# PWR_P12V0A_N12V0A.net
KiCad netlist of a schematic drawn in Altium Designer
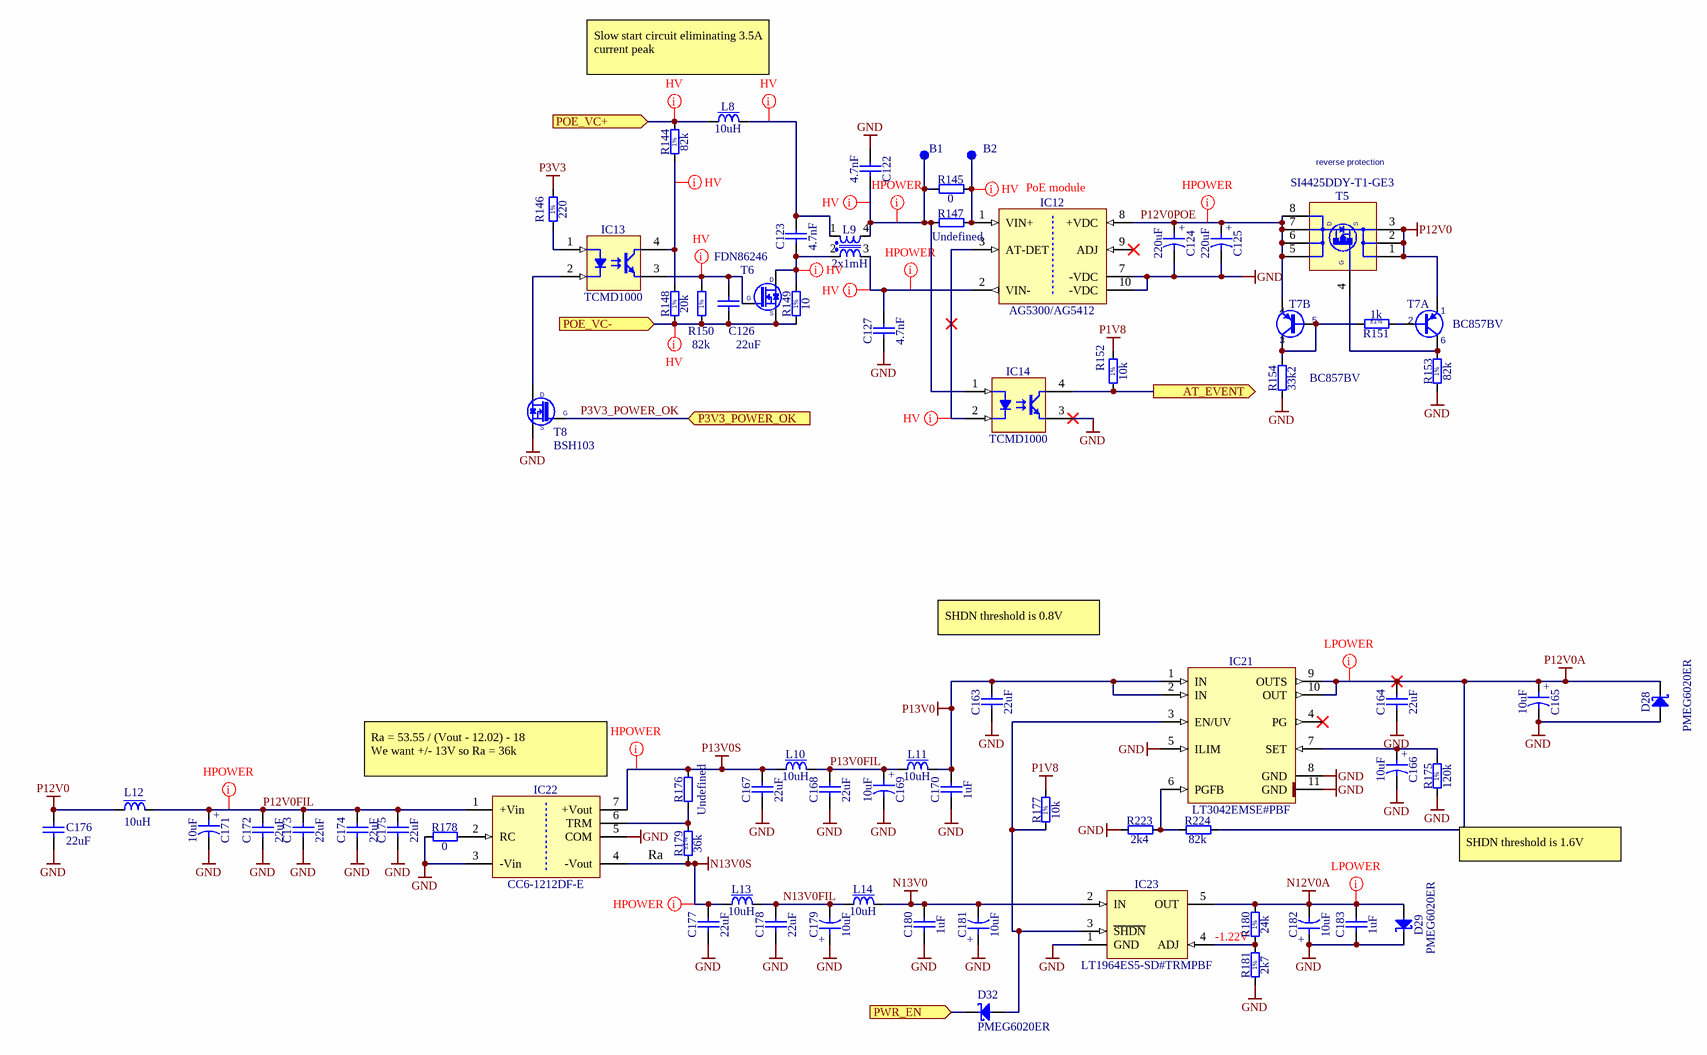
[diagram p0: PWR_P12V0A_N12V0A.SchDoc]

(export (version "E")
  (design (tool "Eeschema 10.0.6"))
  (components
    (comp (ref "B1")
      (value "SMD Pad")
      (footprint "C100")
      (description "Through Hole Pad")
      (fields (field (name "PART NUMBER") "SMD_PAD_D1MM") (field (name "AUTHOR") "CERN DEM JLC"))
      (libsource (lib "Eletro-mechanical") (part "Single SMD Pad (Round)"))
    )
    (comp (ref "B2")
      (value "SMD Pad")
      (footprint "C100")
      (description "Through Hole Pad")
      (fields (field (name "PART NUMBER") "SMD_PAD_D1MM") (field (name "AUTHOR") "CERN DEM JLC"))
      (libsource (lib "Eletro-mechanical") (part "Single SMD Pad (Round)"))
    )
    (comp (ref "C122")
      (value "4.7nF")
      (footprint "CAPC3216X140N")
      (description "Non-polarised capacitor")
      (fields
        (field (name "PART NUMBER") "CC1206_4.7NF_500V_10%_X7R")
        (field (name "VOLTAGE") "500V")
        (field (name "AUTHOR") "GK")
      )
      (libsource (lib "LIBRARY_SCH") (part "CAP_SMD_1206_4.7n_500V"))
    )
    (comp (ref "C123")
      (value "4.7nF")
      (footprint "CAPC3216X140N")
      (description "Non-polarised capacitor")
      (fields
        (field (name "PART NUMBER") "CC1206_4.7NF_500V_10%_X7R")
        (field (name "VOLTAGE") "500V")
        (field (name "AUTHOR") "GK")
      )
      (libsource (lib "LIBRARY_SCH") (part "CAP_SMD_1206_4.7n_500V"))
    )
    (comp (ref "C124")
      (value "220uF")
      (footprint "CAPAE830X620N")
      (description "Polarised capacitor")
      (fields
        (field (name "PART NUMBER") "CAE830-620_220UF_16V_20%")
        (field (name "VOLTAGE") "16V")
        (field (name "AUTHOR") "CERN DEM JLC")
      )
      (libsource (lib "Capacitors") (part "Capacitor - polarized"))
    )
    (comp (ref "C125")
      (value "220uF")
      (footprint "CAPAE830X620N")
      (description "Polarised capacitor")
      (fields
        (field (name "PART NUMBER") "CAE830-620_220UF_16V_20%")
        (field (name "VOLTAGE") "16V")
        (field (name "AUTHOR") "CERN DEM JLC")
      )
      (libsource (lib "Capacitors") (part "Capacitor - polarized"))
    )
    (comp (ref "C126")
      (value "22uF")
      (footprint "CAPC2012X135N")
      (description "Non-polarised capacitor")
      (fields
        (field (name "PART NUMBER") "CC0805_22UF_16V_10%_X5R")
        (field (name "VOLTAGE") "16V")
        (field (name "AUTHOR") "CERN DEM JLC")
      )
      (libsource (lib "Capacitors") (part "Capacitor - non polarized"))
    )
    (comp (ref "C127")
      (value "4.7nF")
      (footprint "CAPC3216X140N")
      (description "Non-polarised capacitor")
      (fields
        (field (name "PART NUMBER") "CC1206_4.7NF_500V_10%_X7R")
        (field (name "VOLTAGE") "500V")
        (field (name "AUTHOR") "GK")
      )
      (libsource (lib "LIBRARY_SCH") (part "CAP_SMD_1206_4.7n_500V"))
    )
    (comp (ref "C163")
      (value "22uF")
      (footprint "CAPC2012X135N")
      (description "Non-polarised capacitor")
      (fields
        (field (name "PART NUMBER") "CC0805_22UF_16V_10%_X5R")
        (field (name "VOLTAGE") "16V")
        (field (name "AUTHOR") "CERN DEM JLC")
      )
      (libsource (lib "Capacitors") (part "Capacitor - non polarized"))
    )
    (comp (ref "C164")
      (value "22uF")
      (footprint "CAPC2012X135N")
      (description "Non-polarised capacitor")
      (fields
        (field (name "PART NUMBER") "CC0805_22UF_16V_10%_X5R")
        (field (name "VOLTAGE") "16V")
        (field (name "AUTHOR") "CERN DEM JLC")
      )
      (libsource (lib "Capacitors") (part "Capacitor - non polarized"))
    )
    (comp (ref "C165")
      (value "10uF")
      (footprint "CAPMP3216X180N")
      (description "Polarised capacitor")
      (fields
        (field (name "PART NUMBER") "CTE3216-18_10UF_16V_20%_AVX_TCJ")
        (field (name "VOLTAGE") "16V")
        (field (name "AUTHOR") "CERN DEM JLC")
      )
      (libsource (lib "Capacitors") (part "Capacitor - polarized"))
    )
    (comp (ref "C166")
      (value "10uF")
      (footprint "CAPMP3216X180N")
      (description "Polarised capacitor")
      (fields
        (field (name "PART NUMBER") "CTE3216-18_10UF_16V_20%_AVX_TCJ")
        (field (name "VOLTAGE") "16V")
        (field (name "AUTHOR") "CERN DEM JLC")
      )
      (libsource (lib "Capacitors") (part "Capacitor - polarized"))
    )
    (comp (ref "C167")
      (value "22uF")
      (footprint "CAPC2012X135N")
      (description "Non-polarised capacitor")
      (fields
        (field (name "PART NUMBER") "CC0805_22UF_16V_10%_X5R")
        (field (name "VOLTAGE") "16V")
        (field (name "AUTHOR") "CERN DEM JLC")
      )
      (libsource (lib "Capacitors") (part "Capacitor - non polarized"))
    )
    (comp (ref "C168")
      (value "22uF")
      (footprint "CAPC2012X135N")
      (description "Non-polarised capacitor")
      (fields
        (field (name "PART NUMBER") "CC0805_22UF_16V_10%_X5R")
        (field (name "VOLTAGE") "16V")
        (field (name "AUTHOR") "CERN DEM JLC")
      )
      (libsource (lib "Capacitors") (part "Capacitor - non polarized"))
    )
    (comp (ref "C169")
      (value "10uF")
      (footprint "CAPMP3216X180N")
      (description "Polarised capacitor")
      (fields
        (field (name "PART NUMBER") "CTE3216-18_10UF_16V_20%_AVX_TCJ")
        (field (name "VOLTAGE") "16V")
        (field (name "AUTHOR") "CERN DEM JLC")
      )
      (libsource (lib "Capacitors") (part "Capacitor - polarized"))
    )
    (comp (ref "C170")
      (value "1uF")
      (footprint "CAPC1005X55N")
      (description "Non-polarised capacitor")
      (fields
        (field (name "PART NUMBER") "CC0402_1UF_16V_10%_X5R")
        (field (name "VOLTAGE") "16V")
        (field (name "AUTHOR") "CERN DEM JLC")
      )
      (libsource (lib "Capacitors") (part "Capacitor - non polarized"))
    )
    (comp (ref "C171")
      (value "10uF")
      (footprint "CAPMP3216X180N")
      (description "Polarised capacitor")
      (fields
        (field (name "PART NUMBER") "CTE3216-18_10UF_16V_20%_AVX_TCJ")
        (field (name "VOLTAGE") "16V")
        (field (name "AUTHOR") "CERN DEM JLC")
      )
      (libsource (lib "Capacitors") (part "Capacitor - polarized"))
    )
    (comp (ref "C172")
      (value "22uF")
      (footprint "CAPC2012X135N")
      (description "Non-polarised capacitor")
      (fields
        (field (name "PART NUMBER") "CC0805_22UF_16V_10%_X5R")
        (field (name "VOLTAGE") "16V")
        (field (name "AUTHOR") "CERN DEM JLC")
      )
      (libsource (lib "Capacitors") (part "Capacitor - non polarized"))
    )
    (comp (ref "C173")
      (value "22uF")
      (footprint "CAPC2012X135N")
      (description "Non-polarised capacitor")
      (fields
        (field (name "PART NUMBER") "CC0805_22UF_16V_10%_X5R")
        (field (name "VOLTAGE") "16V")
        (field (name "AUTHOR") "CERN DEM JLC")
      )
      (libsource (lib "Capacitors") (part "Capacitor - non polarized"))
    )
    (comp (ref "C174")
      (value "22uF")
      (footprint "CAPC2012X135N")
      (description "Non-polarised capacitor")
      (fields
        (field (name "PART NUMBER") "CC0805_22UF_16V_10%_X5R")
        (field (name "VOLTAGE") "16V")
        (field (name "AUTHOR") "CERN DEM JLC")
      )
      (libsource (lib "Capacitors") (part "Capacitor - non polarized"))
    )
    (comp (ref "C175")
      (value "22uF")
      (footprint "CAPC2012X135N")
      (description "Non-polarised capacitor")
      (fields
        (field (name "PART NUMBER") "CC0805_22UF_16V_10%_X5R")
        (field (name "VOLTAGE") "16V")
        (field (name "AUTHOR") "CERN DEM JLC")
      )
      (libsource (lib "Capacitors") (part "Capacitor - non polarized"))
    )
    (comp (ref "C176")
      (value "22uF")
      (footprint "CAPC2012X135N")
      (description "Non-polarised capacitor")
      (fields
        (field (name "PART NUMBER") "CC0805_22UF_16V_10%_X5R")
        (field (name "VOLTAGE") "16V")
        (field (name "AUTHOR") "CERN DEM JLC")
      )
      (libsource (lib "Capacitors") (part "Capacitor - non polarized"))
    )
    (comp (ref "C177")
      (value "22uF")
      (footprint "CAPC2012X135N")
      (description "Non-polarised capacitor")
      (fields
        (field (name "PART NUMBER") "CC0805_22UF_16V_10%_X5R")
        (field (name "VOLTAGE") "16V")
        (field (name "AUTHOR") "CERN DEM JLC")
      )
      (libsource (lib "Capacitors") (part "Capacitor - non polarized"))
    )
    (comp (ref "C178")
      (value "22uF")
      (footprint "CAPC2012X135N")
      (description "Non-polarised capacitor")
      (fields
        (field (name "PART NUMBER") "CC0805_22UF_16V_10%_X5R")
        (field (name "VOLTAGE") "16V")
        (field (name "AUTHOR") "CERN DEM JLC")
      )
      (libsource (lib "Capacitors") (part "Capacitor - non polarized"))
    )
    (comp (ref "C179")
      (value "10uF")
      (footprint "CAPMP3216X180N")
      (description "Polarised capacitor")
      (fields
        (field (name "PART NUMBER") "CTE3216-18_10UF_16V_20%_AVX_TCJ")
        (field (name "VOLTAGE") "16V")
        (field (name "AUTHOR") "CERN DEM JLC")
      )
      (libsource (lib "Capacitors") (part "Capacitor - polarized"))
    )
    (comp (ref "C180")
      (value "1uF")
      (footprint "CAPC1005X55N")
      (description "Non-polarised capacitor")
      (fields
        (field (name "PART NUMBER") "CC0402_1UF_16V_10%_X5R")
        (field (name "VOLTAGE") "16V")
        (field (name "AUTHOR") "CERN DEM JLC")
      )
      (libsource (lib "Capacitors") (part "Capacitor - non polarized"))
    )
    (comp (ref "C181")
      (value "10uF")
      (footprint "CAPMP3216X180N")
      (description "Polarised capacitor")
      (fields
        (field (name "PART NUMBER") "CTE3216-18_10UF_16V_20%_AVX_TCJ")
        (field (name "VOLTAGE") "16V")
        (field (name "AUTHOR") "CERN DEM JLC")
      )
      (libsource (lib "Capacitors") (part "Capacitor - polarized"))
    )
    (comp (ref "C182")
      (value "10uF")
      (footprint "CAPMP3216X180N")
      (description "Polarised capacitor")
      (fields
        (field (name "PART NUMBER") "CTE3216-18_10UF_16V_20%_AVX_TCJ")
        (field (name "VOLTAGE") "16V")
        (field (name "AUTHOR") "CERN DEM JLC")
      )
      (libsource (lib "Capacitors") (part "Capacitor - polarized"))
    )
    (comp (ref "C183")
      (value "1uF")
      (footprint "CAPC1005X55N")
      (description "Non-polarised capacitor")
      (fields
        (field (name "PART NUMBER") "CC0402_1UF_16V_10%_X5R")
        (field (name "VOLTAGE") "16V")
        (field (name "AUTHOR") "CERN DEM JLC")
      )
      (libsource (lib "Capacitors") (part "Capacitor - non polarized"))
    )
    (comp (ref "D28")
      (value "PMEG6020ER")
      (footprint "SODFL3517X110N")
      (description "Schottky Diode")
      (fields
        (field (name "VOLTAGE") "60V")
        (field (name "POWER") "2A")
        (field (name "AUTHOR") "CERN DEM JMW")
      )
      (libsource (lib "ICs And Semiconductors") (part "Diode Schottky"))
    )
    (comp (ref "D29")
      (value "PMEG6020ER")
      (footprint "SODFL3517X110N")
      (description "Schottky Diode")
      (fields
        (field (name "VOLTAGE") "60V")
        (field (name "POWER") "2A")
        (field (name "AUTHOR") "CERN DEM JMW")
      )
      (libsource (lib "ICs And Semiconductors") (part "Diode Schottky"))
    )
    (comp (ref "D32")
      (value "PMEG6020ER")
      (footprint "SODFL3517X110N")
      (description "Schottky Diode")
      (fields
        (field (name "VOLTAGE") "60V")
        (field (name "POWER") "2A")
        (field (name "AUTHOR") "CERN DEM JMW")
      )
      (libsource (lib "ICs And Semiconductors") (part "Diode Schottky"))
    )
    (comp (ref "IC12")
      (value "AG5300/AG5412")
      (footprint "SILVERTEL_AG5300")
      (description "Power-over-Ethernet Plus (POE+) Module")
      (fields (field (name "MANUFACTURER") "SILVERTEL") (field (name "AUTHOR") "CERN DEM JLC"))
      (libsource (lib "ICs And Semiconductors") (part "AG5300"))
    )
    (comp (ref "IC13")
      (value "TCMD1000")
      (footprint "SOIC127P700X242-4N")
      (description "Single Optocoupler")
      (fields
        (field (name "PART NUMBER") "TCMD1000-217-500E")
        (field (name "MANUFACTURER") "VISHAY")
        (field (name "AUTHOR") "GK")
      )
      (libsource (lib "Optoisolators") (part "TCMD1000"))
    )
    (comp (ref "IC14")
      (value "TCMD1000")
      (footprint "SOIC127P700X242-4N")
      (description "Single Optocoupler")
      (fields
        (field (name "PART NUMBER") "TCMD1000-217-500E")
        (field (name "MANUFACTURER") "VISHAY")
        (field (name "AUTHOR") "GK")
      )
      (libsource (lib "Optoisolators") (part "TCMD1000"))
    )
    (comp (ref "IC21")
      (value "LT3042EMSE#PBF")
      (footprint "SOP50P490X110-11N-R168X198")
      (description "20V, 200mA, Ultralow Noise, Ultrahigh PSRR RF Linear Regulator")
      (fields (field (name "MANUFACTURER") "LINEAR TECHNOLOGY") (field (name "AUTHOR") "CERN DEM MR"))
      (libsource (lib "ICs And Semiconductors") (part "LT3042"))
    )
    (comp (ref "IC22")
      (value "CC6-1212DF-E")
      (footprint "CC6-1212DF-E")
      (description "CONV DC/DC 6W DUAL 12V +-12V PCB")
      (fields (field (name "MANUFACTURER") "TDK-Lambda Americas Inc.") (field (name "AUTHOR") "GK"))
      (libsource (lib "LIBRARY_SCH") (part "DC/DC_CC6-1212DF-E"))
    )
    (comp (ref "IC23")
      (value "LT1964ES5-SD#TRMPBF")
      (footprint "SOT95P280X100-5N")
      (description "200mA, Low Noise, Low Dropout Negative Micropower Regulator")
      (fields (field (name "MANUFACTURER") "LINEAR TECHNOLOGY") (field (name "AUTHOR") "CERN DEM JLC"))
      (libsource (lib "ICs And Semiconductors") (part "LT1964-SD"))
    )
    (comp (ref "L8")
      (value "10uH")
      (footprint "IND_MURATA-PS_8400")
      (description "Inductor With Core")
      (fields
        (field (name "PART NUMBER") "IND_10UH_10%_MURATA-PS_8400")
        (field (name "POWER") "950mA")
        (field (name "AUTHOR") "CERN DEM JLC")
      )
      (libsource (lib "Inductors & Transformers") (part "Inductor With Magnetic core"))
    )
    (comp (ref "L9")
      (value "2x1mH")
      (footprint "IND_WURTH_WE-SL2")
      (description "Inductor Common Mode")
      (fields
        (field (name "PART NUMBER") "IND_1MH_50%_WURTH_WE-SL2-744222")
        (field (name "POWER") "800mA")
        (field (name "AUTHOR") "CERN DEM JLC")
      )
      (libsource (lib "Inductors & Transformers") (part "Inductor Common Mode 1Dot-4 2Dot-3"))
    )
    (comp (ref "L10")
      (value "10uH")
      (footprint "IND_MURATA-PS_8400")
      (description "Inductor With Core")
      (fields
        (field (name "PART NUMBER") "IND_10UH_10%_MURATA-PS_8400")
        (field (name "POWER") "950mA")
        (field (name "AUTHOR") "CERN DEM JLC")
      )
      (libsource (lib "Inductors & Transformers") (part "Inductor With Magnetic core"))
    )
    (comp (ref "L11")
      (value "10uH")
      (footprint "IND_MURATA-PS_8400")
      (description "Inductor With Core")
      (fields
        (field (name "PART NUMBER") "IND_10UH_10%_MURATA-PS_8400")
        (field (name "POWER") "950mA")
        (field (name "AUTHOR") "CERN DEM JLC")
      )
      (libsource (lib "Inductors & Transformers") (part "Inductor With Magnetic core"))
    )
    (comp (ref "L12")
      (value "10uH")
      (footprint "IND_MURATA-PS_8400")
      (description "Inductor With Core")
      (fields
        (field (name "PART NUMBER") "IND_10UH_10%_MURATA-PS_8400")
        (field (name "POWER") "950mA")
        (field (name "AUTHOR") "CERN DEM JLC")
      )
      (libsource (lib "Inductors & Transformers") (part "Inductor With Magnetic core"))
    )
    (comp (ref "L13")
      (value "10uH")
      (footprint "IND_MURATA-PS_8400")
      (description "Inductor With Core")
      (fields
        (field (name "PART NUMBER") "IND_10UH_10%_MURATA-PS_8400")
        (field (name "POWER") "950mA")
        (field (name "AUTHOR") "CERN DEM JLC")
      )
      (libsource (lib "Inductors & Transformers") (part "Inductor With Magnetic core"))
    )
    (comp (ref "L14")
      (value "10uH")
      (footprint "IND_MURATA-PS_8400")
      (description "Inductor With Core")
      (fields
        (field (name "PART NUMBER") "IND_10UH_10%_MURATA-PS_8400")
        (field (name "POWER") "950mA")
        (field (name "AUTHOR") "CERN DEM JLC")
      )
      (libsource (lib "Inductors & Transformers") (part "Inductor With Magnetic core"))
    )
    (comp (ref "R144")
      (value "82k")
      (footprint "RESC1608X55N")
      (description "Resistor - 1%")
      (fields
        (field (name "PART NUMBER") "R0603_82K_1%_0.1W_100PPM")
        (field (name "POWER") "0.1W")
        (field (name "AUTHOR") "CERN DEM JLC")
      )
      (libsource (lib "Resistors") (part "Resistor - 1%"))
    )
    (comp (ref "R145")
      (value "0")
      (footprint "RESC1005X40N")
      (description "Resistor")
      (fields
        (field (name "PART NUMBER") "R0402_0R_JUMPER")
        (field (name "MANUFACTURER") "GENERIC")
        (field (name "AUTHOR") "CERN DEM JLC")
      )
      (libsource (lib "Resistors") (part "Resistor"))
    )
    (comp (ref "R146")
      (value "220")
      (footprint "RESC1608X55N")
      (description "Resistor - 1%")
      (fields
        (field (name "PART NUMBER") "R0603_220R_1%_0.1W_100PPM")
        (field (name "POWER") "0.1W")
        (field (name "AUTHOR") "CERN DEM JLC")
      )
      (libsource (lib "Resistors") (part "Resistor - 1%"))
    )
    (comp (ref "R147")
      (value "Undefined")
      (footprint "RESC1608X55N")
      (description "Resistor")
      (fields (field (name "PART NUMBER") "R0603_NO-VALUE") (field (name "AUTHOR") "CERN DEM JLC"))
      (libsource (lib "Resistors") (part "Resistor"))
    )
    (comp (ref "R148")
      (value "20k")
      (footprint "RESC1005X40N")
      (description "Resistor - 1%")
      (fields
        (field (name "PART NUMBER") "R0402_20K_1%_0.0625W_100PPM")
        (field (name "POWER") "0.0625W")
        (field (name "AUTHOR") "CERN DEM JLC")
      )
      (libsource (lib "") (part "Resistor - 1%_1"))
    )
    (comp (ref "R149")
      (value "10")
      (footprint "RESC1005X40N")
      (description "Resistor - 1%")
      (fields
        (field (name "PART NUMBER") "R0402_10R_1%_0.0625W_200PPM")
        (field (name "POWER") "0.0625W")
        (field (name "AUTHOR") "CERN DEM JLC")
      )
      (libsource (lib "") (part "Resistor - 1%_1"))
    )
    (comp (ref "R150")
      (value "82k")
      (footprint "RESC1608X55N")
      (description "Resistor - 1%")
      (fields
        (field (name "PART NUMBER") "R0603_82K_1%_0.1W_100PPM")
        (field (name "POWER") "0.1W")
        (field (name "AUTHOR") "CERN DEM JLC")
      )
      (libsource (lib "Resistors") (part "Resistor - 1%"))
    )
    (comp (ref "R151")
      (value "1k")
      (footprint "RESC1005X40N")
      (description "Resistor - 1%")
      (fields
        (field (name "PART NUMBER") "R0402_1K_1%_0.0625W_100PPM")
        (field (name "POWER") "0.0625W")
        (field (name "TOLERANCE") "±1%")
        (field (name "AUTHOR") "CERN DEM JLC")
      )
      (libsource (lib "") (part "Resistor - 1%_1"))
    )
    (comp (ref "R152")
      (value "10k")
      (footprint "RESC1005X40N")
      (description "Resistor - 1%")
      (fields
        (field (name "PART NUMBER") "R0402_10K_1%_0.0625W_100PPM")
        (field (name "POWER") "0.0625W")
        (field (name "AUTHOR") "CERN DEM JLC")
      )
      (libsource (lib "") (part "Resistor - 1%_1"))
    )
    (comp (ref "R153")
      (value "82k")
      (footprint "RESC1608X55N")
      (description "Resistor - 1%")
      (fields
        (field (name "PART NUMBER") "R0603_82K_1%_0.1W_100PPM")
        (field (name "POWER") "0.1W")
        (field (name "AUTHOR") "CERN DEM JLC")
      )
      (libsource (lib "Resistors") (part "Resistor - 1%"))
    )
    (comp (ref "R154")
      (value "33k2")
      (footprint "RESC1608X55N")
      (description "Resistor - 0.1%")
      (fields
        (field (name "PART NUMBER") "R0603_33K2_0.1%_0.063W_10PPM")
        (field (name "POWER") "0.063W")
        (field (name "AUTHOR") "CERN DEM JLC")
      )
      (libsource (lib "Resistors") (part "Resistor - 0.1%"))
    )
    (comp (ref "R175")
      (value "120k")
      (footprint "RESC1608X55N")
      (description "Resistor - 1%")
      (fields
        (field (name "PART NUMBER") "R0603_120K_1%_0.1W_100PPM")
        (field (name "POWER") "0.1W")
        (field (name "AUTHOR") "CERN DEM JLC")
      )
      (libsource (lib "Resistors") (part "Resistor - 1%"))
    )
    (comp (ref "R176")
      (value "Undefined")
      (footprint "RESC1608X55N")
      (description "Resistor")
      (fields (field (name "PART NUMBER") "R0603_NO-VALUE") (field (name "AUTHOR") "CERN DEM JLC"))
      (libsource (lib "Resistors") (part "Resistor"))
    )
    (comp (ref "R177")
      (value "10k")
      (footprint "RESC1005X40N")
      (description "Resistor - 1%")
      (fields
        (field (name "PART NUMBER") "R0402_10K_1%_0.0625W_100PPM")
        (field (name "POWER") "0.0625W")
        (field (name "AUTHOR") "CERN DEM JLC")
      )
      (libsource (lib "") (part "Resistor - 1%_1"))
    )
    (comp (ref "R178")
      (value "0")
      (footprint "RESC1005X40N")
      (description "Resistor")
      (fields
        (field (name "PART NUMBER") "R0402_0R_JUMPER")
        (field (name "MANUFACTURER") "GENERIC")
        (field (name "AUTHOR") "CERN DEM JLC")
      )
      (libsource (lib "Resistors") (part "Resistor"))
    )
    (comp (ref "R179")
      (value "36k")
      (footprint "RESC1005X40N")
      (description "Resistor - 1%")
      (fields
        (field (name "PART NUMBER") "R0402_36K_1%_0.0625W_100PPM")
        (field (name "POWER") "0.0625W")
        (field (name "TOLERANCE") "±1%")
        (field (name "AUTHOR") "CERN DEM JLC")
      )
      (libsource (lib "") (part "Resistor - 1%_1"))
    )
    (comp (ref "R180")
      (value "24k")
      (footprint "RESC1608X55N")
      (description "Resistor - 1%")
      (fields
        (field (name "PART NUMBER") "R0603_24K_1%_0.1W_100PPM")
        (field (name "POWER") "0.1W")
        (field (name "AUTHOR") "CERN DEM JLC")
      )
      (libsource (lib "Resistors") (part "Resistor - 1%"))
    )
    (comp (ref "R181")
      (value "2k7")
      (footprint "RESC1608X55N")
      (description "Resistor - 1%")
      (fields
        (field (name "PART NUMBER") "R0603_2K7_1%_0.1W_100PPM")
        (field (name "POWER") "0.1W")
        (field (name "AUTHOR") "CERN DEM JLC")
      )
      (libsource (lib "Resistors") (part "Resistor - 1%"))
    )
    (comp (ref "R223")
      (value "2k4")
      (footprint "RESC1005X40N")
      (description "Resistor - 1%")
      (fields
        (field (name "PART NUMBER") "R0402_2K4_1%_0.0625W_100PPM")
        (field (name "POWER") "0.0625W")
        (field (name "AUTHOR") "CERN DEM JLC")
      )
      (libsource (lib "") (part "Resistor - 1%_1"))
    )
    (comp (ref "R224")
      (value "82k")
      (footprint "RESC1608X55N")
      (description "Resistor - 1%")
      (fields
        (field (name "PART NUMBER") "R0603_82K_1%_0.1W_100PPM")
        (field (name "POWER") "0.1W")
        (field (name "AUTHOR") "CERN DEM JLC")
      )
      (libsource (lib "") (part "Resistor - 1%_1"))
    )
    (comp (ref "T5")
      (value "SI4425DDY-T1-GE3")
      (footprint "SOIC127P600X175-8N")
      (description "-30V -19.7A P-Channel MOSFET")
      (fields (field (name "MANUFACTURER") "VISHAY SILICONIX") (field (name "AUTHOR") "CERN DEM MR"))
      (libsource (lib "ICs And Semiconductors") (part "SI4425DDY"))
    )
    (comp (ref "T6")
      (value "FDN86246")
      (footprint "SOT95P237X112-3N")
      (description "N-CHANNEL MOSFET WITH DIODE")
      (fields (field (name "MANUFACTURER") "ON SEMICONDUCTOR") (field (name "AUTHOR") "CERN DEM BC"))
      (libsource (lib "") (part "N-MOSFET-D 1G 2S 3D_1"))
    )
    (comp (ref "T7")
      (value "BC857BV")
      (footprint "SOTFL50P160X60-6N")
      (description "45V, 100mA PNP General Purpose Double Transistor")
      (fields (field (name "MANUFACTURER") "NXP SEMICONDUCTORS") (field (name "AUTHOR") "CERN DEM JLC"))
      (libsource (lib "ICs And Semiconductors") (part "BC857BV"))
    )
    (comp (ref "T8")
      (value "BSH103")
      (footprint "SOT95P230X110-3N")
      (description "N-CHANNEL MOSFET WITH DIODE")
      (fields (field (name "MANUFACTURER") "NEXPERIA") (field (name "AUTHOR") "CERN DEM JLC"))
      (libsource (lib "ICs And Semiconductors") (part "N-MOSFET-D 1G 2S 3D"))
    )
  )
  (nets
    (net (code "1") (name "/AT_EVENT") (class "Default")
      (node (ref "IC14") (pin "4") (pinfunction "C_4") (pintype "open_collector"))
      (node (ref "R152") (pin "1") (pinfunction "1_1") (pintype "passive"))
    )
    (net (code "2") (name "/N13V0FIL") (class "Default")
      (node (ref "C178") (pin "2") (pinfunction "2_2") (pintype "passive"))
      (node (ref "C179") (pin "2") (pinfunction "2_2") (pintype "passive"))
      (node (ref "L13") (pin "2") (pinfunction "2_2") (pintype "passive"))
      (node (ref "L14") (pin "1") (pinfunction "1_1") (pintype "passive"))
    )
    (net (code "3") (name "/P3V3_POWER_OK") (class "Default")
      (node (ref "T8") (pin "1") (pinfunction "G_1") (pintype "passive"))
    )
    (net (code "4") (name "/P12V0FIL") (class "Default")
      (node (ref "C171") (pin "1") (pinfunction "1_1") (pintype "passive"))
      (node (ref "C172") (pin "2") (pinfunction "2_2") (pintype "passive"))
      (node (ref "C173") (pin "2") (pinfunction "2_2") (pintype "passive"))
      (node (ref "C174") (pin "2") (pinfunction "2_2") (pintype "passive"))
      (node (ref "C175") (pin "2") (pinfunction "2_2") (pintype "passive"))
      (node (ref "IC22") (pin "1") (pinfunction "+Vin_1") (pintype "power_in"))
      (node (ref "L12") (pin "2") (pinfunction "2_2") (pintype "passive"))
    )
    (net (code "5") (name "/P12V0POE") (class "Default")
      (node (ref "C124") (pin "1") (pinfunction "1_1") (pintype "passive"))
      (node (ref "C125") (pin "1") (pinfunction "1_1") (pintype "passive"))
      (node (ref "IC12") (pin "8") (pinfunction "+VDC_8") (pintype "input"))
      (node (ref "T5") (pin "5") (pinfunction "D_5") (pintype "passive"))
      (node (ref "T5") (pin "6") (pinfunction "D_6") (pintype "passive"))
      (node (ref "T5") (pin "7") (pinfunction "D_7") (pintype "passive"))
      (node (ref "T5") (pin "8") (pinfunction "D_8") (pintype "passive"))
      (node (ref "T7") (pin "4") (pinfunction "E_4") (pintype "passive"))
    )
    (net (code "6") (name "/P13V0FIL") (class "Default")
      (node (ref "C168") (pin "2") (pinfunction "2_2") (pintype "passive"))
      (node (ref "C169") (pin "1") (pinfunction "1_1") (pintype "passive"))
      (node (ref "L10") (pin "2") (pinfunction "2_2") (pintype "passive"))
      (node (ref "L11") (pin "1") (pinfunction "1_1") (pintype "passive"))
    )
    (net (code "7") (name "/POE_VC+") (class "Default")
      (node (ref "L8") (pin "1") (pinfunction "1_1") (pintype "passive"))
      (node (ref "R144") (pin "2") (pinfunction "2_2") (pintype "passive"))
    )
    (net (code "8") (name "/POE_VC-") (class "Default")
      (node (ref "C126") (pin "1") (pinfunction "1_1") (pintype "passive"))
      (node (ref "R148") (pin "1") (pinfunction "1_1") (pintype "passive"))
      (node (ref "R149") (pin "1") (pinfunction "1_1") (pintype "passive"))
      (node (ref "R150") (pin "1") (pinfunction "1_1") (pintype "passive"))
      (node (ref "T6") (pin "2") (pinfunction "S_2") (pintype "passive"))
    )
    (net (code "9") (name "/PWR_EN") (class "Default")
      (node (ref "D32") (pin "1") (pinfunction "C_1") (pintype "passive"))
    )
    (net (code "10") (name "GND") (class "Default")
      (node (ref "C122") (pin "1") (pinfunction "1_1") (pintype "passive"))
      (node (ref "C124") (pin "2") (pinfunction "2_2") (pintype "passive"))
      (node (ref "C125") (pin "2") (pinfunction "2_2") (pintype "passive"))
      (node (ref "C127") (pin "1") (pinfunction "1_1") (pintype "passive"))
      (node (ref "C163") (pin "1") (pinfunction "1_1") (pintype "passive"))
      (node (ref "C164") (pin "1") (pinfunction "1_1") (pintype "passive"))
      (node (ref "C165") (pin "2") (pinfunction "2_2") (pintype "passive"))
      (node (ref "C166") (pin "2") (pinfunction "2_2") (pintype "passive"))
      (node (ref "C167") (pin "1") (pinfunction "1_1") (pintype "passive"))
      (node (ref "C168") (pin "1") (pinfunction "1_1") (pintype "passive"))
      (node (ref "C169") (pin "2") (pinfunction "2_2") (pintype "passive"))
      (node (ref "C170") (pin "1") (pinfunction "1_1") (pintype "passive"))
      (node (ref "C171") (pin "2") (pinfunction "2_2") (pintype "passive"))
      (node (ref "C172") (pin "1") (pinfunction "1_1") (pintype "passive"))
      (node (ref "C173") (pin "1") (pinfunction "1_1") (pintype "passive"))
      (node (ref "C174") (pin "1") (pinfunction "1_1") (pintype "passive"))
      (node (ref "C175") (pin "1") (pinfunction "1_1") (pintype "passive"))
      (node (ref "C176") (pin "1") (pinfunction "1_1") (pintype "passive"))
      (node (ref "C177") (pin "1") (pinfunction "1_1") (pintype "passive"))
      (node (ref "C178") (pin "1") (pinfunction "1_1") (pintype "passive"))
      (node (ref "C179") (pin "1") (pinfunction "1_1") (pintype "passive"))
      (node (ref "C180") (pin "1") (pinfunction "1_1") (pintype "passive"))
      (node (ref "C181") (pin "1") (pinfunction "1_1") (pintype "passive"))
      (node (ref "C182") (pin "1") (pinfunction "1_1") (pintype "passive"))
      (node (ref "C183") (pin "1") (pinfunction "1_1") (pintype "passive"))
      (node (ref "D28") (pin "2") (pinfunction "A_2") (pintype "passive"))
      (node (ref "D29") (pin "1") (pinfunction "C_1") (pintype "passive"))
      (node (ref "IC12") (pin "10") (pinfunction "-VDC_10") (pintype "power_in"))
      (node (ref "IC12") (pin "7") (pinfunction "-VDC_7") (pintype "power_in"))
      (node (ref "IC14") (pin "3") (pinfunction "E_3") (pintype "open_emitter"))
      (node (ref "IC21") (pin "11") (pinfunction "GND_11") (pintype "power_in"))
      (node (ref "IC21") (pin "5") (pinfunction "ILIM_5") (pintype "input"))
      (node (ref "IC21") (pin "8") (pinfunction "GND_8") (pintype "power_in"))
      (node (ref "IC22") (pin "3") (pinfunction "-Vin_3") (pintype "power_in"))
      (node (ref "IC22") (pin "5") (pinfunction "COM_5") (pintype "power_in"))
      (node (ref "IC23") (pin "1") (pinfunction "GND_1") (pintype "power_in"))
      (node (ref "R153") (pin "1") (pinfunction "1_1") (pintype "passive"))
      (node (ref "R154") (pin "1") (pinfunction "1_1") (pintype "passive"))
      (node (ref "R175") (pin "1") (pinfunction "1_1") (pintype "passive"))
      (node (ref "R178") (pin "1") (pinfunction "1_1") (pintype "passive"))
      (node (ref "R181") (pin "1") (pinfunction "1_1") (pintype "passive"))
      (node (ref "R223") (pin "1") (pinfunction "1_1") (pintype "passive"))
      (node (ref "T8") (pin "2") (pinfunction "S_2") (pintype "passive"))
    )
    (net (code "11") (name "N12V0A") (class "Default")
      (node (ref "C182") (pin "2") (pinfunction "2_2") (pintype "passive"))
      (node (ref "C183") (pin "2") (pinfunction "2_2") (pintype "passive"))
      (node (ref "D29") (pin "2") (pinfunction "A_2") (pintype "passive"))
      (node (ref "IC23") (pin "5") (pinfunction "OUT_5") (pintype "power_in"))
      (node (ref "R180") (pin "2") (pinfunction "2_2") (pintype "passive"))
    )
    (net (code "12") (name "N13V0") (class "Default")
      (node (ref "C180") (pin "2") (pinfunction "2_2") (pintype "passive"))
      (node (ref "C181") (pin "2") (pinfunction "2_2") (pintype "passive"))
      (node (ref "IC23") (pin "2") (pinfunction "IN_2") (pintype "input"))
      (node (ref "L14") (pin "2") (pinfunction "2_2") (pintype "passive"))
    )
    (net (code "13") (name "N13V0S") (class "Default")
      (node (ref "C177") (pin "2") (pinfunction "2_2") (pintype "passive"))
      (node (ref "IC22") (pin "4") (pinfunction "-Vout_4") (pintype "power_in"))
      (node (ref "L13") (pin "1") (pinfunction "1_1") (pintype "passive"))
      (node (ref "R179") (pin "1") (pinfunction "1_1") (pintype "passive"))
    )
    (net (code "14") (name "Net-(C123-Pad2)") (class "Default")
      (node (ref "C123") (pin "2") (pinfunction "2_2") (pintype "passive"))
      (node (ref "L8") (pin "2") (pinfunction "2_2") (pintype "passive"))
      (node (ref "L9") (pin "1") (pinfunction "1_1") (pintype "passive"))
    )
    (net (code "15") (name "Net-(D32-A)") (class "Default")
      (node (ref "D32") (pin "2") (pinfunction "A_2") (pintype "passive"))
      (node (ref "IC21") (pin "3") (pinfunction "EN/UV_3") (pintype "input"))
      (node (ref "IC23") (pin "3") (pinfunction "~{SHDN}_3") (pintype "input"))
      (node (ref "R177") (pin "1") (pinfunction "1_1") (pintype "passive"))
    )
    (net (code "16") (name "Net-(IC12-AT-DET)") (class "Default")
      (node (ref "IC12") (pin "3") (pinfunction "AT-DET_3") (pintype "input"))
      (node (ref "IC14") (pin "2") (pinfunction "C_2") (pintype "input"))
    )
    (net (code "17") (name "Net-(IC12-VIN+)") (class "Default")
      (node (ref "B2") (pin "1") (pinfunction "1_1") (pintype "bidirectional"))
      (node (ref "IC12") (pin "1") (pinfunction "VIN+_1") (pintype "input"))
      (node (ref "R145") (pin "2") (pinfunction "2_2") (pintype "passive"))
      (node (ref "R147") (pin "2") (pinfunction "2_2") (pintype "passive"))
    )
    (net (code "18") (name "Net-(IC12-VIN-)") (class "Default")
      (node (ref "C127") (pin "2") (pinfunction "2_2") (pintype "passive"))
      (node (ref "IC12") (pin "2") (pinfunction "VIN-_2") (pintype "output"))
      (node (ref "L9") (pin "3") (pinfunction "3_3") (pintype "passive"))
    )
    (net (code "19") (name "Net-(IC13-A)") (class "Default")
      (node (ref "IC13") (pin "1") (pinfunction "A_1") (pintype "input"))
      (node (ref "R146") (pin "1") (pinfunction "1_1") (pintype "passive"))
    )
    (net (code "20") (name "Net-(IC13-C-Pad4)") (class "Default")
      (node (ref "IC13") (pin "4") (pinfunction "C_4") (pintype "open_collector"))
      (node (ref "R144") (pin "1") (pinfunction "1_1") (pintype "passive"))
      (node (ref "R148") (pin "2") (pinfunction "2_2") (pintype "passive"))
    )
    (net (code "21") (name "Net-(IC13-E)") (class "Default")
      (node (ref "C126") (pin "2") (pinfunction "2_2") (pintype "passive"))
      (node (ref "IC13") (pin "3") (pinfunction "E_3") (pintype "open_emitter"))
      (node (ref "R150") (pin "2") (pinfunction "2_2") (pintype "passive"))
      (node (ref "T6") (pin "1") (pinfunction "G_1") (pintype "passive"))
    )
    (net (code "22") (name "Net-(IC14-A)") (class "Default")
      (node (ref "B1") (pin "1") (pinfunction "1_1") (pintype "bidirectional"))
      (node (ref "C122") (pin "2") (pinfunction "2_2") (pintype "passive"))
      (node (ref "IC14") (pin "1") (pinfunction "A_1") (pintype "input"))
      (node (ref "L9") (pin "4") (pinfunction "4_4") (pintype "passive"))
      (node (ref "R145") (pin "1") (pinfunction "1_1") (pintype "passive"))
      (node (ref "R147") (pin "1") (pinfunction "1_1") (pintype "passive"))
    )
    (net (code "23") (name "Net-(IC21-PGFB)") (class "Default")
      (node (ref "IC21") (pin "6") (pinfunction "PGFB_6") (pintype "input"))
      (node (ref "R223") (pin "2") (pinfunction "2_2") (pintype "passive"))
      (node (ref "R224") (pin "1") (pinfunction "1_1") (pintype "passive"))
    )
    (net (code "24") (name "Net-(IC21-SET)") (class "Default")
      (node (ref "C166") (pin "1") (pinfunction "1_1") (pintype "passive"))
      (node (ref "IC21") (pin "7") (pinfunction "SET_7") (pintype "input"))
      (node (ref "R175") (pin "2") (pinfunction "2_2") (pintype "passive"))
    )
    (net (code "25") (name "Net-(IC22-RC)") (class "Default")
      (node (ref "IC22") (pin "2") (pinfunction "RC_2") (pintype "input"))
      (node (ref "R178") (pin "2") (pinfunction "2_2") (pintype "passive"))
    )
    (net (code "26") (name "Net-(IC22-TRM)") (class "Default")
      (node (ref "IC22") (pin "6") (pinfunction "TRM_6") (pintype "power_in"))
      (node (ref "R176") (pin "1") (pinfunction "1_1") (pintype "passive"))
      (node (ref "R179") (pin "2") (pinfunction "2_2") (pintype "passive"))
    )
    (net (code "27") (name "Net-(IC23-ADJ)") (class "Default")
      (node (ref "IC23") (pin "4") (pinfunction "ADJ_4") (pintype "input"))
      (node (ref "R180") (pin "1") (pinfunction "1_1") (pintype "passive"))
      (node (ref "R181") (pin "2") (pinfunction "2_2") (pintype "passive"))
    )
    (net (code "28") (name "Net-(T6-D)") (class "Default")
      (node (ref "C123") (pin "1") (pinfunction "1_1") (pintype "passive"))
      (node (ref "L9") (pin "2") (pinfunction "2_2") (pintype "passive"))
      (node (ref "R149") (pin "2") (pinfunction "2_2") (pintype "passive"))
      (node (ref "T6") (pin "3") (pinfunction "D_3") (pintype "passive"))
    )
    (net (code "29") (name "Net-(T7A-B)") (class "Default")
      (node (ref "R151") (pin "1") (pinfunction "1_1") (pintype "passive"))
      (node (ref "T7") (pin "2") (pinfunction "B_2") (pintype "passive"))
    )
    (net (code "30") (name "Net-(T7A-C)") (class "Default")
      (node (ref "R153") (pin "2") (pinfunction "2_2") (pintype "passive"))
      (node (ref "T5") (pin "4") (pinfunction "S_4") (pintype "passive"))
      (node (ref "T7") (pin "6") (pinfunction "C_6") (pintype "passive"))
    )
    (net (code "31") (name "Net-(T7B-B)") (class "Default")
      (node (ref "R151") (pin "2") (pinfunction "2_2") (pintype "passive"))
      (node (ref "R154") (pin "2") (pinfunction "2_2") (pintype "passive"))
      (node (ref "T7") (pin "3") (pinfunction "C_3") (pintype "passive"))
      (node (ref "T7") (pin "5") (pinfunction "B_5") (pintype "passive"))
    )
    (net (code "32") (name "Net-(T8-D)") (class "Default")
      (node (ref "IC13") (pin "2") (pinfunction "C_2") (pintype "input"))
      (node (ref "T8") (pin "3") (pinfunction "D_3") (pintype "passive"))
    )
    (net (code "33") (name "P1V8") (class "Default")
      (node (ref "R152") (pin "2") (pinfunction "2_2") (pintype "passive"))
      (node (ref "R177") (pin "2") (pinfunction "2_2") (pintype "passive"))
    )
    (net (code "34") (name "P3V3") (class "Default")
      (node (ref "R146") (pin "2") (pinfunction "2_2") (pintype "passive"))
    )
    (net (code "35") (name "P12V0") (class "Default")
      (node (ref "C176") (pin "2") (pinfunction "2_2") (pintype "passive"))
      (node (ref "L12") (pin "1") (pinfunction "1_1") (pintype "passive"))
      (node (ref "T5") (pin "1") (pinfunction "S_1") (pintype "passive"))
      (node (ref "T5") (pin "2") (pinfunction "S_2") (pintype "passive"))
      (node (ref "T5") (pin "3") (pinfunction "S_3") (pintype "passive"))
      (node (ref "T7") (pin "1") (pinfunction "E_1") (pintype "passive"))
    )
    (net (code "36") (name "P12V0A") (class "Default")
      (node (ref "C164") (pin "2") (pinfunction "2_2") (pintype "passive"))
      (node (ref "C165") (pin "1") (pinfunction "1_1") (pintype "passive"))
      (node (ref "D28") (pin "1") (pinfunction "C_1") (pintype "passive"))
      (node (ref "IC21") (pin "10") (pinfunction "OUT_10") (pintype "output"))
      (node (ref "IC21") (pin "9") (pinfunction "OUTS_9") (pintype "output"))
      (node (ref "R224") (pin "2") (pinfunction "2_2") (pintype "passive"))
    )
    (net (code "37") (name "P13V0") (class "Default")
      (node (ref "C163") (pin "2") (pinfunction "2_2") (pintype "passive"))
      (node (ref "C170") (pin "2") (pinfunction "2_2") (pintype "passive"))
      (node (ref "IC21") (pin "1") (pinfunction "IN_1") (pintype "input"))
      (node (ref "IC21") (pin "2") (pinfunction "IN_2") (pintype "input"))
      (node (ref "L11") (pin "2") (pinfunction "2_2") (pintype "passive"))
    )
    (net (code "38") (name "P13V0S") (class "Default")
      (node (ref "C167") (pin "2") (pinfunction "2_2") (pintype "passive"))
      (node (ref "IC22") (pin "7") (pinfunction "+Vout_7") (pintype "power_in"))
      (node (ref "L10") (pin "1") (pinfunction "1_1") (pintype "passive"))
      (node (ref "R176") (pin "2") (pinfunction "2_2") (pintype "passive"))
    )
    (net (code "39") (name "unconnected-(IC12-ADJ-Pad9)") (class "Default")
      (node (ref "IC12") (pin "9") (pinfunction "ADJ_9") (pintype "input+no_connect"))
    )
    (net (code "40") (name "unconnected-(IC21-PG-Pad4)") (class "Default")
      (node (ref "IC21") (pin "4") (pinfunction "PG_4") (pintype "output+no_connect"))
    )
  )
)
